# C210_0003_SARA_Module.net
KiCad netlist of a schematic drawn in Altium Designer
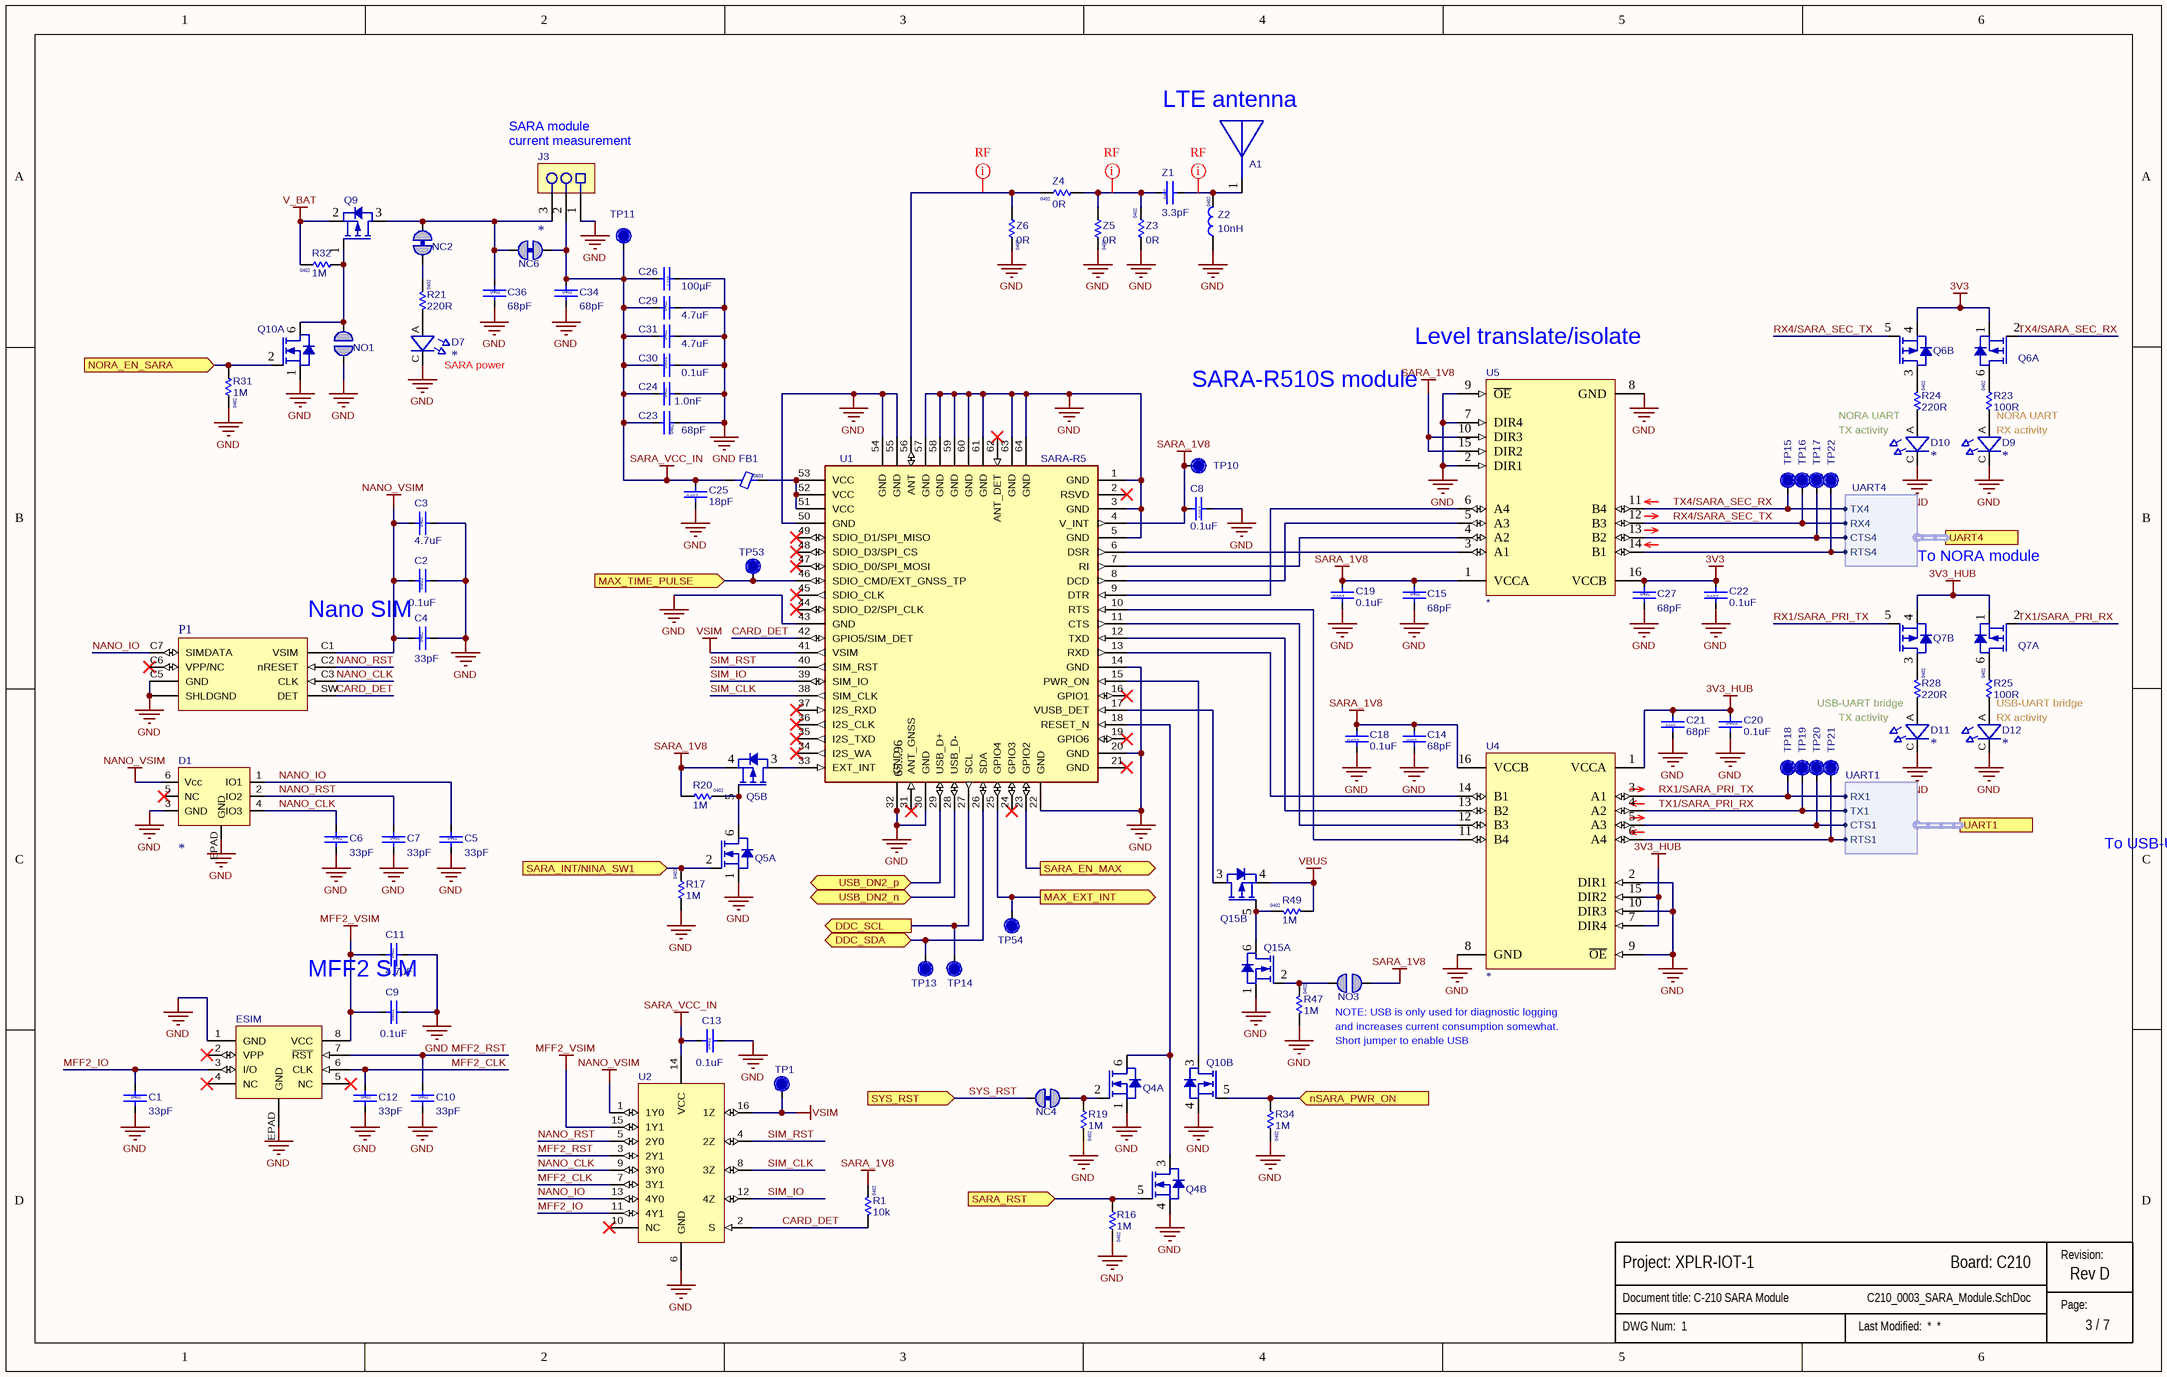
[diagram p0: C210_0003_SARA_Module.SchDoc]

(export (version "E")
  (design (tool "Eeschema 10.0.6"))
  (components
    (comp (ref "A1")
      (value "PCS.66.A")
      (footprint "PCS.66.A")
      (description "RF Passive, Antenna, LTE, 600-6000MHz, Monopole")
      (fields (field (name "VOLTAGE") "None"))
      (libsource (lib "PCS.66.A") (part "PCS.66.A"))
    )
    (comp (ref "C1")
      (value "33pF")
      (footprint "Cap 0402 HD")
      (description "Cap, Ceramic,  33pF, 50V, 5%, NPO, 0402")
      (fields
        (field (name "SIZE") "0402")
        (field (name "PART NUMBER") "120-00045")
        (field (name "TOLERANCE") "+/- 5%")
      )
      (libsource (lib "Arena_Parts_DB_Lib") (part "Cap Chip"))
    )
    (comp (ref "C2")
      (value "0.1uF")
      (footprint "Cap 0402 HD")
      (description "Cap, Ceramic 0.1uF 10V 10% X5R 0402")
      (fields
        (field (name "SIZE") "0402")
        (field (name "PART NUMBER") "120-00016")
        (field (name "MANUFACTURER") "Murata Electronics North America")
      )
      (libsource (lib "Arena_Parts_DB_Lib") (part "Cap Chip"))
    )
    (comp (ref "C3")
      (value "4.7uF")
      (footprint "Cap 0402 HD")
      (description "Cap, Ceramic 4.7uF 10V 20% X5R 0402")
      (fields
        (field (name "SIZE") "0402")
        (field (name "PART NUMBER") "120-00020")
        (field (name "TOLERANCE") "+/- 20%")
      )
      (libsource (lib "Arena_Parts_DB_Lib") (part "Cap Chip"))
    )
    (comp (ref "C4")
      (value "33pF")
      (footprint "Cap 0402 HD")
      (description "Cap, Ceramic,  33pF, 50V, 5%, NPO, 0402")
      (fields
        (field (name "SIZE") "0402")
        (field (name "PART NUMBER") "120-00045")
        (field (name "TOLERANCE") "+/- 5%")
      )
      (libsource (lib "Arena_Parts_DB_Lib") (part "Cap Chip"))
    )
    (comp (ref "C5")
      (value "33pF")
      (footprint "Cap 0402 HD")
      (description "Cap, Ceramic,  33pF, 50V, 5%, NPO, 0402")
      (fields
        (field (name "SIZE") "0402")
        (field (name "PART NUMBER") "120-00045")
        (field (name "TOLERANCE") "+/- 5%")
      )
      (libsource (lib "Arena_Parts_DB_Lib") (part "Cap Chip"))
    )
    (comp (ref "C6")
      (value "33pF")
      (footprint "Cap 0402 HD")
      (description "Cap, Ceramic,  33pF, 50V, 5%, NPO, 0402")
      (fields
        (field (name "SIZE") "0402")
        (field (name "PART NUMBER") "120-00045")
        (field (name "TOLERANCE") "+/- 5%")
      )
      (libsource (lib "Arena_Parts_DB_Lib") (part "Cap Chip"))
    )
    (comp (ref "C7")
      (value "33pF")
      (footprint "Cap 0402 HD")
      (description "Cap, Ceramic,  33pF, 50V, 5%, NPO, 0402")
      (fields
        (field (name "SIZE") "0402")
        (field (name "PART NUMBER") "120-00045")
        (field (name "TOLERANCE") "+/- 5%")
      )
      (libsource (lib "Arena_Parts_DB_Lib") (part "Cap Chip"))
    )
    (comp (ref "C8")
      (value "0.1uF")
      (footprint "Cap 0402 HD")
      (description "Cap, Ceramic 0.1uF 10V 10% X5R 0402")
      (fields
        (field (name "SIZE") "0402")
        (field (name "PART NUMBER") "120-00016")
        (field (name "MANUFACTURER") "Murata Electronics North America")
      )
      (libsource (lib "Arena_Parts_DB_Lib") (part "Cap Chip"))
    )
    (comp (ref "C9")
      (value "0.1uF")
      (footprint "Cap 0402 HD")
      (description "Cap, Ceramic 0.1uF 10V 10% X5R 0402")
      (fields
        (field (name "SIZE") "0402")
        (field (name "PART NUMBER") "120-00016")
        (field (name "MANUFACTURER") "Murata Electronics North America")
      )
      (libsource (lib "Arena_Parts_DB_Lib") (part "Cap Chip"))
    )
    (comp (ref "C10")
      (value "33pF")
      (footprint "Cap 0402 HD")
      (description "Cap, Ceramic,  33pF, 50V, 5%, NPO, 0402")
      (fields
        (field (name "SIZE") "0402")
        (field (name "PART NUMBER") "120-00045")
        (field (name "TOLERANCE") "+/- 5%")
      )
      (libsource (lib "Arena_Parts_DB_Lib") (part "Cap Chip"))
    )
    (comp (ref "C11")
      (value "4.7uF")
      (footprint "Cap 0402 HD")
      (description "Cap, Ceramic 4.7uF 10V 20% X5R 0402")
      (fields
        (field (name "SIZE") "0402")
        (field (name "PART NUMBER") "120-00020")
        (field (name "TOLERANCE") "+/- 20%")
      )
      (libsource (lib "Arena_Parts_DB_Lib") (part "Cap Chip"))
    )
    (comp (ref "C12")
      (value "33pF")
      (footprint "Cap 0402 HD")
      (description "Cap, Ceramic,  33pF, 50V, 5%, NPO, 0402")
      (fields
        (field (name "SIZE") "0402")
        (field (name "PART NUMBER") "120-00045")
        (field (name "TOLERANCE") "+/- 5%")
      )
      (libsource (lib "Arena_Parts_DB_Lib") (part "Cap Chip"))
    )
    (comp (ref "C13")
      (value "0.1uF")
      (footprint "Cap 0402 HD")
      (description "Cap, Ceramic 0.1uF 10V 10% X5R 0402")
      (fields
        (field (name "SIZE") "0402")
        (field (name "PART NUMBER") "120-00016")
        (field (name "MANUFACTURER") "Murata Electronics North America")
      )
      (libsource (lib "Arena_Parts_DB_Lib") (part "Cap Chip"))
    )
    (comp (ref "C14")
      (value "68pF")
      (footprint "Cap 0402 HD")
      (description "Cap, Ceramic, 68pF, 50V, 1%, NP0, 0402")
      (fields
        (field (name "SIZE") "0402")
        (field (name "PART NUMBER") "120-00047")
        (field (name "TOLERANCE") "+/- 1%")
      )
      (libsource (lib "Arena_Parts_DB_Lib") (part "Cap Chip"))
    )
    (comp (ref "C15")
      (value "68pF")
      (footprint "Cap 0402 HD")
      (description "Cap, Ceramic, 68pF, 50V, 1%, NP0, 0402")
      (fields
        (field (name "SIZE") "0402")
        (field (name "PART NUMBER") "120-00047")
        (field (name "TOLERANCE") "+/- 1%")
      )
      (libsource (lib "Arena_Parts_DB_Lib") (part "Cap Chip"))
    )
    (comp (ref "C18")
      (value "0.1uF")
      (footprint "Cap 0402 HD")
      (description "Cap, Ceramic 0.1uF 10V 10% X5R 0402")
      (fields
        (field (name "SIZE") "0402")
        (field (name "PART NUMBER") "120-00016")
        (field (name "MANUFACTURER") "Murata Electronics North America")
      )
      (libsource (lib "Arena_Parts_DB_Lib") (part "Cap Chip"))
    )
    (comp (ref "C19")
      (value "0.1uF")
      (footprint "Cap 0402 HD")
      (description "Cap, Ceramic 0.1uF 10V 10% X5R 0402")
      (fields
        (field (name "SIZE") "0402")
        (field (name "PART NUMBER") "120-00016")
        (field (name "MANUFACTURER") "Murata Electronics North America")
      )
      (libsource (lib "Arena_Parts_DB_Lib") (part "Cap Chip"))
    )
    (comp (ref "C20")
      (value "0.1uF")
      (footprint "Cap 0402 HD")
      (description "Cap, Ceramic 0.1uF 10V 10% X5R 0402")
      (fields
        (field (name "SIZE") "0402")
        (field (name "PART NUMBER") "120-00016")
        (field (name "MANUFACTURER") "Murata Electronics North America")
      )
      (libsource (lib "Arena_Parts_DB_Lib") (part "Cap Chip"))
    )
    (comp (ref "C21")
      (value "68pF")
      (footprint "Cap 0402 HD")
      (description "Cap, Ceramic, 68pF, 50V, 1%, NP0, 0402")
      (fields
        (field (name "SIZE") "0402")
        (field (name "PART NUMBER") "120-00047")
        (field (name "TOLERANCE") "+/- 1%")
      )
      (libsource (lib "Arena_Parts_DB_Lib") (part "Cap Chip"))
    )
    (comp (ref "C22")
      (value "0.1uF")
      (footprint "Cap 0402 HD")
      (description "Cap, Ceramic 0.1uF 10V 10% X5R 0402")
      (fields
        (field (name "SIZE") "0402")
        (field (name "PART NUMBER") "120-00016")
        (field (name "MANUFACTURER") "Murata Electronics North America")
      )
      (libsource (lib "Arena_Parts_DB_Lib") (part "Cap Chip"))
    )
    (comp (ref "C23")
      (value "68pF")
      (footprint "Cap 0402 HD")
      (description "Cap, Ceramic, 68pF, 50V, 1%, NP0, 0402")
      (fields
        (field (name "SIZE") "0402")
        (field (name "PART NUMBER") "120-00047")
        (field (name "TOLERANCE") "+/- 1%")
      )
      (libsource (lib "Arena_Parts_DB_Lib") (part "Cap Chip"))
    )
    (comp (ref "C24")
      (value "1.0nF")
      (footprint "Cap 0402 HD")
      (description "CAP CER 1.0nF 50V 10% X7R 0402")
      (fields
        (field (name "SIZE") "0402")
        (field (name "PART NUMBER") "120-00010")
        (field (name "TOLERANCE") "+/- 10%")
      )
      (libsource (lib "Arena_Parts_DB_Lib") (part "Cap Chip"))
    )
    (comp (ref "C25")
      (value "18pF")
      (footprint "Cap 0402 HD")
      (description "Cap, Ceramic 18pF 50V 5% NP0 0402")
      (fields
        (field (name "SIZE") "0402")
        (field (name "PART NUMBER") "120-00041")
        (field (name "TOLERANCE") "+/- 5%")
      )
      (libsource (lib "Arena_Parts_DB_Lib") (part "Cap Chip"))
    )
    (comp (ref "C26")
      (value "100µF")
      (footprint "Cap 1210")
      (description "100µF ±20% 10V Ceramic Capacitor X5R 1210 (3225 Metric)")
      (fields
        (field (name "SIZE") "1210")
        (field (name "PART NUMBER") "120-00223")
        (field (name "TOLERANCE") "+/- 20%")
      )
      (libsource (lib "Arena_Parts_DB_Lib") (part "Cap Chip"))
    )
    (comp (ref "C27")
      (value "68pF")
      (footprint "Cap 0402 HD")
      (description "Cap, Ceramic, 68pF, 50V, 1%, NP0, 0402")
      (fields
        (field (name "SIZE") "0402")
        (field (name "PART NUMBER") "120-00047")
        (field (name "TOLERANCE") "+/- 1%")
      )
      (libsource (lib "Arena_Parts_DB_Lib") (part "Cap Chip"))
    )
    (comp (ref "C29")
      (value "4.7uF")
      (footprint "Cap 0402 HD")
      (description "Cap, Ceramic 4.7uF 10V 20% X5R 0402")
      (fields
        (field (name "SIZE") "0402")
        (field (name "PART NUMBER") "120-00020")
        (field (name "TOLERANCE") "+/- 20%")
      )
      (libsource (lib "Arena_Parts_DB_Lib") (part "Cap Chip"))
    )
    (comp (ref "C30")
      (value "0.1uF")
      (footprint "Cap 0402 HD")
      (description "Cap, Ceramic 0.1uF 10V 10% X5R 0402")
      (fields
        (field (name "SIZE") "0402")
        (field (name "PART NUMBER") "120-00016")
        (field (name "MANUFACTURER") "Murata Electronics North America")
      )
      (libsource (lib "Arena_Parts_DB_Lib") (part "Cap Chip"))
    )
    (comp (ref "C31")
      (value "4.7uF")
      (footprint "Cap 0402 HD")
      (description "Cap, Ceramic 4.7uF 10V 20% X5R 0402")
      (fields
        (field (name "SIZE") "0402")
        (field (name "PART NUMBER") "120-00020")
        (field (name "TOLERANCE") "+/- 20%")
      )
      (libsource (lib "Arena_Parts_DB_Lib") (part "Cap Chip"))
    )
    (comp (ref "C34")
      (value "68pF")
      (footprint "Cap 0402 HD")
      (description "Cap, Ceramic, 68pF, 50V, 1%, NP0, 0402")
      (fields
        (field (name "SIZE") "0402")
        (field (name "PART NUMBER") "120-00047")
        (field (name "TOLERANCE") "+/- 1%")
      )
      (libsource (lib "Arena_Parts_DB_Lib") (part "Cap Chip"))
    )
    (comp (ref "C36")
      (value "68pF")
      (footprint "Cap 0402 HD")
      (description "Cap, Ceramic, 68pF, 50V, 1%, NP0, 0402")
      (fields
        (field (name "SIZE") "0402")
        (field (name "PART NUMBER") "120-00047")
        (field (name "TOLERANCE") "+/- 1%")
      )
      (libsource (lib "Arena_Parts_DB_Lib") (part "Cap Chip"))
    )
    (comp (ref "D1")
      (value "~")
      (footprint "TPD3E001DRSR")
      (description "TVS Diode, ESD High Speed 3-Channel Array, WSON-6, 3mmX3mm")
      (fields (field (name "VOLTAGE") "5.5V") (field (name "MANUFACTURER P/N") "*"))
      (libsource (lib "TPD3E001DRSR") (part "TPD3E001"))
    )
    (comp (ref "D7")
      (value "LTST-C190EKT")
      (footprint "LTST-C190EKT")
      (description "DIODE, LED, SMT, Red, CLEAR LENS, 2.0V 10mA, 0603")
      (fields (field (name "VOLTAGE") "2.0V") (field (name "COLOR") "*"))
      (libsource (lib "LTST-C190EKT") (part "LTST-C190EKT"))
    )
    (comp (ref "D9")
      (value "LTST-C190YKT")
      (footprint "LTST-C190YKT")
      (description "DIODE, LED, SMT, YELLOW, CLEAR LENS, 2.1V 10mA, 0603")
      (fields (field (name "VOLTAGE") "2.1V") (field (name "COLOR") "*"))
      (libsource (lib "LTST-C190YKT") (part "LTST-C190YKT"))
    )
    (comp (ref "D10")
      (value "115-00019")
      (footprint "LTST-C190KGKT")
      (description "DIODE, LED, SMT, GREEN, CLEAR LENS, 2.0V 20mA, 0603")
      (fields (field (name "VOLTAGE") "2.0V") (field (name "COLOR") "*"))
      (libsource (lib "LTST-C190KGKT") (part "LTST-C190KGKT"))
    )
    (comp (ref "D11")
      (value "115-00019")
      (footprint "LTST-C190KGKT")
      (description "DIODE, LED, SMT, GREEN, CLEAR LENS, 2.0V 20mA, 0603")
      (fields (field (name "VOLTAGE") "2.0V") (field (name "COLOR") "*"))
      (libsource (lib "LTST-C190KGKT") (part "LTST-C190KGKT"))
    )
    (comp (ref "D12")
      (value "LTST-C190YKT")
      (footprint "LTST-C190YKT")
      (description "DIODE, LED, SMT, YELLOW, CLEAR LENS, 2.1V 10mA, 0603")
      (fields (field (name "VOLTAGE") "2.1V") (field (name "COLOR") "*"))
      (libsource (lib "LTST-C190YKT") (part "LTST-C190YKT"))
    )
    (comp (ref "ESIM")
      (value "MFF2 SIM")
      (footprint "MFF2 SIM")
      (description "ESIM, SMT, MFF2, 1.8V, SMT, VFDFPN8, 5mmX6mm")
      (fields (field (name "VOLTAGE") "1.8V"))
      (libsource (lib "MFF2") (part "MFF2 SIM"))
    )
    (comp (ref "FB1")
      (value "BLM18EG221SN1")
      (footprint "BLM18EG221SN1")
      (description "Ferrite Bead, 220ohm @ 100MHz, 2A, 0603")
      (fields (field (name "VOLTAGE") "None") (field (name "SIZE") "0603"))
      (libsource (lib "BLM18EG221SN1") (part "BLM18EG221SN1"))
    )
    (comp (ref "J3")
      (value "130-00105")
      (footprint "HDR-0.1P-3Pin-1Row-SMT")
      (description "Header, 0.100\" Pitch, 3 Pin, Vertical SMT, Black")
      (fields (field (name "MANUFACTURER P/N") "*") (field (name "VOLTAGE") "None"))
      (libsource (lib "Arena_Parts_DB_Lib") (part "CON-3Pin_1Row"))
    )
    (comp (ref "NC2")
      (value "Solderbridge-ShortDNP")
      (footprint "Solderbridge-Short")
      (description "Solderbridge-Short")
      (fields (field (name "ADDED BY") "Paul B"))
      (libsource (lib "PCB_Misc") (part "Solderbridge-Short"))
    )
    (comp (ref "NC4")
      (value "Solderbridge-ShortDNP")
      (footprint "Solderbridge-Short")
      (description "Solderbridge-Short")
      (fields (field (name "ADDED BY") "Paul B"))
      (libsource (lib "") (part "Solderbridge-Short_1"))
    )
    (comp (ref "NC6")
      (value "Solderbridge-ShortDNP")
      (footprint "Solderbridge-Short")
      (description "Solderbridge-Short")
      (fields (field (name "ADDED BY") "Paul B"))
      (libsource (lib "") (part "Solderbridge-Short_1"))
    )
    (comp (ref "NO1")
      (value "Solderbridge-OpenDNP")
      (footprint "Solderbridge-Open")
      (description "Solderbridge-Open")
      (fields (field (name "ADDED BY") "Paul B"))
      (libsource (lib "PCB_Misc") (part "Solderbridge-Open"))
    )
    (comp (ref "NO3")
      (value "Solderbridge-OpenDNP")
      (footprint "Solderbridge-Open")
      (description "Solderbridge-Open")
      (fields (field (name "ADDED BY") "Paul B"))
      (libsource (lib "PCB_Misc") (part "Solderbridge-Open"))
    )
    (comp (ref "P1")
      (value "G85D1160022HHR")
      (footprint "G85D1160022HHR")
      (description "NANO SIM SOCKET, SWITCH, SMT, HINGED, 13mmX14mm")
      (fields (field (name "VOLTAGE") "5V"))
      (libsource (lib "DM3CS-SF") (part "G85D1160022HHR"))
    )
    (comp (ref "Q4")
      (value "140-00016")
      (footprint "SOT-563")
      (description "MOSFET 2N-CH 20V 0.8A, SOT-563")
      (fields (field (name "VOLTAGE") "20V"))
      (libsource (lib "Arena_Parts_DB_Lib") (part "MOSFET-N-Dual"))
    )
    (comp (ref "Q5")
      (value "140-00030")
      (footprint "SOT-563")
      (description "MOSFET N/P-CH 20V SOT-563, 540 mA, −430 mA")
      (fields (field (name "VOLTAGE") "20V"))
      (libsource (lib "Arena_Parts_DB_Lib") (part "MOSFET-N-P_Pair"))
    )
    (comp (ref "Q6")
      (value "FDY2000PZ")
      (footprint "FDY2000PZ")
      (description "MOSFET DUAL P-CH 20V SOT-563, -350mA")
      (fields (field (name "VOLTAGE") "20V"))
      (libsource (lib "FDY2000PZ") (part "MOSFET-Dual-P_Chan"))
    )
    (comp (ref "Q7")
      (value "FDY2000PZ")
      (footprint "FDY2000PZ")
      (description "MOSFET DUAL P-CH 20V SOT-563, -350mA")
      (fields (field (name "VOLTAGE") "20V"))
      (libsource (lib "FDY2000PZ") (part "MOSFET-Dual-P_Chan"))
    )
    (comp (ref "Q9")
      (value "140-00008")
      (footprint "SOT-23")
      (description "P-MOSFET, 20V 3.1A, SOT-23")
      (fields (field (name "VOLTAGE") "20V"))
      (libsource (lib "Arena_Parts_DB_Lib") (part "MOSFET-P"))
    )
    (comp (ref "Q10")
      (value "140-00016")
      (footprint "SOT-563")
      (description "MOSFET 2N-CH 20V 0.8A, SOT-563")
      (fields (field (name "VOLTAGE") "20V"))
      (libsource (lib "Arena_Parts_DB_Lib") (part "MOSFET-N-Dual"))
    )
    (comp (ref "Q15")
      (value "140-00030")
      (footprint "SOT-563")
      (description "MOSFET N/P-CH 20V SOT-563, 540 mA, −430 mA")
      (fields (field (name "VOLTAGE") "20V"))
      (libsource (lib "Arena_Parts_DB_Lib") (part "MOSFET-N-P_Pair"))
    )
    (comp (ref "R1")
      (value "10k")
      (footprint "RES 0402 HD")
      (description "Resistor 10k ohm 1% 1/16W, 0402")
      (fields
        (field (name "SIZE") "0402")
        (field (name "PART NUMBER") "180-00024")
        (field (name "POWER") "1/16W")
      )
      (libsource (lib "Arena_Parts_DB_Lib") (part "Res sm"))
    )
    (comp (ref "R16")
      (value "1M")
      (footprint "RES 0402 HD")
      (description "Resistor 1M ohm 1%, 1/16W, 0402")
      (fields
        (field (name "SIZE") "0402")
        (field (name "PART NUMBER") "180-00054")
        (field (name "POWER") "1/16W")
      )
      (libsource (lib "Arena_Parts_DB_Lib") (part "Res sm"))
    )
    (comp (ref "R17")
      (value "1M")
      (footprint "RES 0402 HD")
      (description "Resistor 1M ohm 1%, 1/16W, 0402")
      (fields
        (field (name "SIZE") "0402")
        (field (name "PART NUMBER") "180-00054")
        (field (name "POWER") "1/16W")
      )
      (libsource (lib "Arena_Parts_DB_Lib") (part "Res sm"))
    )
    (comp (ref "R19")
      (value "1M")
      (footprint "RES 0402 HD")
      (description "Resistor 1M ohm 1%, 1/16W, 0402")
      (fields
        (field (name "SIZE") "0402")
        (field (name "PART NUMBER") "180-00054")
        (field (name "POWER") "1/16W")
      )
      (libsource (lib "Arena_Parts_DB_Lib") (part "Res sm"))
    )
    (comp (ref "R20")
      (value "1M")
      (footprint "RES 0402 HD")
      (description "Resistor 1M ohm 1%, 1/16W, 0402")
      (fields
        (field (name "SIZE") "0402")
        (field (name "PART NUMBER") "180-00054")
        (field (name "POWER") "1/16W")
      )
      (libsource (lib "Arena_Parts_DB_Lib") (part "Res sm"))
    )
    (comp (ref "R21")
      (value "220R")
      (footprint "RES 0402 HD")
      (description "Resistor, 220ohm, 5%, 1/16W, 0402.")
      (fields
        (field (name "SIZE") "0402")
        (field (name "PART NUMBER") "180-00098")
        (field (name "MANUFACTURER") "Panasonic Electronic Components")
      )
      (libsource (lib "Arena_Parts_DB_Lib") (part "Res sm"))
    )
    (comp (ref "R23")
      (value "100R")
      (footprint "RES 0402 HD")
      (description "Resistor, 100ohm, 1%, 1/16W, 0402.")
      (fields
        (field (name "SIZE") "0402")
        (field (name "PART NUMBER") "180-00051")
        (field (name "POWER") "1/16W")
      )
      (libsource (lib "Arena_Parts_DB_Lib") (part "Res sm"))
    )
    (comp (ref "R24")
      (value "220R")
      (footprint "RES 0402 HD")
      (description "Resistor, 220ohm, 5%, 1/16W, 0402.")
      (fields
        (field (name "SIZE") "0402")
        (field (name "PART NUMBER") "180-00098")
        (field (name "MANUFACTURER") "Panasonic Electronic Components")
      )
      (libsource (lib "Arena_Parts_DB_Lib") (part "Res sm"))
    )
    (comp (ref "R25")
      (value "100R")
      (footprint "RES 0402 HD")
      (description "Resistor, 100ohm, 1%, 1/16W, 0402.")
      (fields
        (field (name "SIZE") "0402")
        (field (name "PART NUMBER") "180-00051")
        (field (name "POWER") "1/16W")
      )
      (libsource (lib "Arena_Parts_DB_Lib") (part "Res sm"))
    )
    (comp (ref "R28")
      (value "220R")
      (footprint "RES 0402 HD")
      (description "Resistor, 220ohm, 5%, 1/16W, 0402.")
      (fields
        (field (name "SIZE") "0402")
        (field (name "PART NUMBER") "180-00098")
        (field (name "MANUFACTURER") "Panasonic Electronic Components")
      )
      (libsource (lib "Arena_Parts_DB_Lib") (part "Res sm"))
    )
    (comp (ref "R31")
      (value "1M")
      (footprint "RES 0402 HD")
      (description "Resistor 1M ohm 1%, 1/16W, 0402")
      (fields
        (field (name "SIZE") "0402")
        (field (name "PART NUMBER") "180-00054")
        (field (name "POWER") "1/16W")
      )
      (libsource (lib "Arena_Parts_DB_Lib") (part "Res sm"))
    )
    (comp (ref "R32")
      (value "1M")
      (footprint "RES 0402 HD")
      (description "Resistor 1M ohm 1%, 1/16W, 0402")
      (fields
        (field (name "SIZE") "0402")
        (field (name "PART NUMBER") "180-00054")
        (field (name "POWER") "1/16W")
      )
      (libsource (lib "Arena_Parts_DB_Lib") (part "Res sm"))
    )
    (comp (ref "R34")
      (value "1M")
      (footprint "RES 0402 HD")
      (description "Resistor 1M ohm 1%, 1/16W, 0402")
      (fields
        (field (name "SIZE") "0402")
        (field (name "PART NUMBER") "180-00054")
        (field (name "POWER") "1/16W")
      )
      (libsource (lib "Arena_Parts_DB_Lib") (part "Res sm"))
    )
    (comp (ref "R47")
      (value "1M")
      (footprint "RES 0402 HD")
      (description "Resistor 1M ohm 1%, 1/16W, 0402")
      (fields
        (field (name "SIZE") "0402")
        (field (name "PART NUMBER") "180-00054")
        (field (name "POWER") "1/16W")
      )
      (libsource (lib "Arena_Parts_DB_Lib") (part "Res sm"))
    )
    (comp (ref "R49")
      (value "1M")
      (footprint "RES 0402 HD")
      (description "Resistor 1M ohm 1%, 1/16W, 0402")
      (fields
        (field (name "SIZE") "0402")
        (field (name "PART NUMBER") "180-00054")
        (field (name "POWER") "1/16W")
      )
      (libsource (lib "Arena_Parts_DB_Lib") (part "Res sm"))
    )
    (comp (ref "TP1")
      (value "TP")
      (footprint "TP12R")
      (description "Testpoint, Round 1.0mm Dia")
      (fields
        (field (name "PART NUMBER") "TP10R")
        (field (name "ADDED BY") "Jeremy D")
        (field (name "CHECKED BY") "Paul B")
      )
      (libsource (lib "PCB_Misc") (part "TP_R"))
    )
    (comp (ref "TP10")
      (value "TP")
      (footprint "TP12R")
      (description "Testpoint, Round 1.0mm Dia")
      (fields
        (field (name "PART NUMBER") "TP10R")
        (field (name "ADDED BY") "Jeremy D")
        (field (name "CHECKED BY") "Paul B")
      )
      (libsource (lib "PCB_Misc") (part "TP_R"))
    )
    (comp (ref "TP11")
      (value "TP")
      (footprint "TP12R")
      (description "Testpoint, Round 1.0mm Dia")
      (fields
        (field (name "PART NUMBER") "TP10R")
        (field (name "ADDED BY") "Jeremy D")
        (field (name "CHECKED BY") "Paul B")
      )
      (libsource (lib "PCB_Misc") (part "TP_R"))
    )
    (comp (ref "TP13")
      (value "TP")
      (footprint "TP12R")
      (description "Testpoint, Round 1.0mm Dia")
      (fields
        (field (name "PART NUMBER") "TP10R")
        (field (name "ADDED BY") "Jeremy D")
        (field (name "CHECKED BY") "Paul B")
      )
      (libsource (lib "PCB_Misc") (part "TP_R"))
    )
    (comp (ref "TP14")
      (value "TP")
      (footprint "TP12R")
      (description "Testpoint, Round 1.0mm Dia")
      (fields
        (field (name "PART NUMBER") "TP10R")
        (field (name "ADDED BY") "Jeremy D")
        (field (name "CHECKED BY") "Paul B")
      )
      (libsource (lib "PCB_Misc") (part "TP_R"))
    )
    (comp (ref "TP15")
      (value "TP")
      (footprint "TP12R")
      (description "Testpoint, Round 1.0mm Dia")
      (fields
        (field (name "PART NUMBER") "TP10R")
        (field (name "ADDED BY") "Jeremy D")
        (field (name "CHECKED BY") "Paul B")
      )
      (libsource (lib "PCB_Misc") (part "TP_R"))
    )
    (comp (ref "TP16")
      (value "TP")
      (footprint "TP12R")
      (description "Testpoint, Round 1.0mm Dia")
      (fields
        (field (name "PART NUMBER") "TP10R")
        (field (name "ADDED BY") "Jeremy D")
        (field (name "CHECKED BY") "Paul B")
      )
      (libsource (lib "PCB_Misc") (part "TP_R"))
    )
    (comp (ref "TP17")
      (value "TP")
      (footprint "TP12R")
      (description "Testpoint, Round 1.0mm Dia")
      (fields
        (field (name "PART NUMBER") "TP10R")
        (field (name "ADDED BY") "Jeremy D")
        (field (name "CHECKED BY") "Paul B")
      )
      (libsource (lib "PCB_Misc") (part "TP_R"))
    )
    (comp (ref "TP18")
      (value "TP")
      (footprint "TP12R")
      (description "Testpoint, Round 1.0mm Dia")
      (fields
        (field (name "PART NUMBER") "TP10R")
        (field (name "ADDED BY") "Jeremy D")
        (field (name "CHECKED BY") "Paul B")
      )
      (libsource (lib "PCB_Misc") (part "TP_R"))
    )
    (comp (ref "TP19")
      (value "TP")
      (footprint "TP12R")
      (description "Testpoint, Round 1.0mm Dia")
      (fields
        (field (name "PART NUMBER") "TP10R")
        (field (name "ADDED BY") "Jeremy D")
        (field (name "CHECKED BY") "Paul B")
      )
      (libsource (lib "PCB_Misc") (part "TP_R"))
    )
    (comp (ref "TP20")
      (value "TP")
      (footprint "TP12R")
      (description "Testpoint, Round 1.0mm Dia")
      (fields
        (field (name "PART NUMBER") "TP10R")
        (field (name "ADDED BY") "Jeremy D")
        (field (name "CHECKED BY") "Paul B")
      )
      (libsource (lib "PCB_Misc") (part "TP_R"))
    )
    (comp (ref "TP21")
      (value "TP")
      (footprint "TP12R")
      (description "Testpoint, Round 1.0mm Dia")
      (fields
        (field (name "PART NUMBER") "TP10R")
        (field (name "ADDED BY") "Jeremy D")
        (field (name "CHECKED BY") "Paul B")
      )
      (libsource (lib "PCB_Misc") (part "TP_R"))
    )
    (comp (ref "TP22")
      (value "TP")
      (footprint "TP12R")
      (description "Testpoint, Round 1.0mm Dia")
      (fields
        (field (name "PART NUMBER") "TP10R")
        (field (name "ADDED BY") "Jeremy D")
        (field (name "CHECKED BY") "Paul B")
      )
      (libsource (lib "PCB_Misc") (part "TP_R"))
    )
    (comp (ref "TP53")
      (value "TP")
      (footprint "TP12R")
      (description "Testpoint, Round 1.0mm Dia")
      (fields
        (field (name "PART NUMBER") "TP10R")
        (field (name "ADDED BY") "Jeremy D")
        (field (name "CHECKED BY") "Paul B")
      )
      (libsource (lib "PCB_Misc") (part "TP_R"))
    )
    (comp (ref "TP54")
      (value "TP")
      (footprint "TP12R")
      (description "Testpoint, Round 1.0mm Dia")
      (fields
        (field (name "PART NUMBER") "TP10R")
        (field (name "ADDED BY") "Jeremy D")
        (field (name "CHECKED BY") "Paul B")
      )
      (libsource (lib "PCB_Misc") (part "TP_R"))
    )
    (comp (ref "U1")
      (value "SARA-R5")
      (footprint "SARA-XX")
      (description "GSM/GPRS and GSM/EGPRS/HSPA Cellular Module")
      (fields (field (name "MANUFACTURER") "u-blox"))
      (libsource (lib "ubloxLib") (part "SARA-R5"))
    )
    (comp (ref "U2")
      (value "NX3DV2567")
      (footprint "XQFN-16")
      (description "IC, ANLG SWITCH, 4PDT, SIM OPTIMIZED, 1.4V-4.3V, SMT, XQFN-16, 2.6mmX1.8mm")
      (fields (field (name "VOLTAGE") "1.4V-4.3V"))
      (libsource (lib "NX3DV2567") (part "NX3DV2567"))
    )
    (comp (ref "U4")
      (value "225-00011")
      (footprint "QFN0.5P2x6-16Pin_W-Pad")
      (description "Voltage Level Translator Bidirectional 1 Circuit 4 Channel 380Mbps 16-DHVQFN (2.5x3.5)")
      (fields (field (name "MANUFACTURER P/N") "*") (field (name "VOLTAGE") "3.6V"))
      (libsource (lib "") (part "74AVC4TD245_1"))
    )
    (comp (ref "U5")
      (value "225-00011")
      (footprint "QFN0.5P2x6-16Pin_W-Pad")
      (description "Voltage Level Translator Bidirectional 1 Circuit 4 Channel 380Mbps 16-DHVQFN (2.5x3.5)")
      (fields (field (name "MANUFACTURER P/N") "*") (field (name "VOLTAGE") "3.6V"))
      (libsource (lib "Arena_Parts_DB_Lib") (part "74AVC4TD245"))
    )
    (comp (ref "Z1")
      (value "3.3pF")
      (footprint "Cap 0402 HD")
      (description "CAP CER 3.3PF 50V +/-0.25pF NP0 0402")
      (fields
        (field (name "SIZE") "0402")
        (field (name "PART NUMBER") "120-00079")
        (field (name "TOLERANCE") "Other")
      )
      (libsource (lib "Arena_Parts_DB_Lib") (part "Cap Chip"))
    )
    (comp (ref "Z2")
      (value "10nH")
      (footprint "IND 0402")
      (description "INDUCTOR 10NH 300MA 0402")
      (fields
        (field (name "SIZE") "0402")
        (field (name "PART NUMBER") "150-00010")
        (field (name "TOLERANCE") "+/- 5%")
      )
      (libsource (lib "Arena_Parts_DB_Lib") (part "Ind sm"))
    )
    (comp (ref "Z3")
      (value "0R")
      (footprint "RES 0402 HD")
      (description "Resistor 0 ohm 1/16W 0402")
      (fields
        (field (name "SIZE") "0402")
        (field (name "PART NUMBER") "180-00020")
        (field (name "POWER") "1/16W")
      )
      (libsource (lib "Arena_Parts_DB_Lib") (part "Res sm"))
    )
    (comp (ref "Z4")
      (value "0R")
      (footprint "RES 0402 HD")
      (description "Resistor 0 ohm 1/16W 0402")
      (fields
        (field (name "SIZE") "0402")
        (field (name "PART NUMBER") "180-00020")
        (field (name "POWER") "1/16W")
      )
      (libsource (lib "Arena_Parts_DB_Lib") (part "Res sm"))
    )
    (comp (ref "Z5")
      (value "0R")
      (footprint "RES 0402 HD")
      (description "Resistor 0 ohm 1/16W 0402")
      (fields
        (field (name "SIZE") "0402")
        (field (name "PART NUMBER") "180-00020")
        (field (name "POWER") "1/16W")
      )
      (libsource (lib "Arena_Parts_DB_Lib") (part "Res sm"))
    )
    (comp (ref "Z6")
      (value "0R")
      (footprint "RES 0402 HD")
      (description "Resistor 0 ohm 1/16W 0402")
      (fields
        (field (name "SIZE") "0402")
        (field (name "PART NUMBER") "180-00020")
        (field (name "POWER") "1/16W")
      )
      (libsource (lib "Arena_Parts_DB_Lib") (part "Res sm"))
    )
  )
  (nets
    (net (code "3") (name "/CARD_DET") (class "Default")
      (node (ref "P1") (pin "SW") (pinfunction "DET_SW") (pintype "passive"))
      (node (ref "R1") (pin "1") (pinfunction "1_1") (pintype "passive"))
      (node (ref "U1") (pin "42") (pinfunction "GPIO5/SIM_DET_42") (pintype "bidirectional"))
      (node (ref "U2") (pin "2") (pinfunction "S_2") (pintype "input"))
    )
    (net (code "4") (name "/DDC_SCL") (class "Default")
      (node (ref "TP14") (pin "1") (pintype "passive"))
      (node (ref "U1") (pin "27") (pinfunction "SCL_27") (pintype "output"))
    )
    (net (code "5") (name "/DDC_SDA") (class "Default")
      (node (ref "TP13") (pin "1") (pintype "passive"))
      (node (ref "U1") (pin "26") (pinfunction "SDA_26") (pintype "bidirectional"))
    )
    (net (code "6") (name "/MAX_EXT_INT") (class "Default")
      (node (ref "TP54") (pin "1") (pintype "passive"))
      (node (ref "U1") (pin "25") (pinfunction "GPIO4_25") (pintype "bidirectional"))
    )
    (net (code "7") (name "/MAX_TIME_PULSE") (class "Default")
      (node (ref "TP53") (pin "1") (pintype "passive"))
      (node (ref "U1") (pin "46") (pinfunction "SDIO_CMD/EXT_GNSS_TP_46") (pintype "bidirectional"))
    )
    (net (code "8") (name "/MFF2_CLK") (class "Default")
      (node (ref "C12") (pin "1") (pinfunction "1_1") (pintype "passive"))
      (node (ref "ESIM") (pin "6") (pinfunction "CLK_6") (pintype "input"))
      (node (ref "U2") (pin "7") (pinfunction "3Y1_7") (pintype "bidirectional"))
    )
    (net (code "9") (name "/MFF2_IO") (class "Default")
      (node (ref "C1") (pin "1") (pinfunction "1_1") (pintype "passive"))
      (node (ref "ESIM") (pin "3") (pinfunction "I/O_3") (pintype "bidirectional"))
      (node (ref "U2") (pin "11") (pinfunction "4Y1_11") (pintype "bidirectional"))
    )
    (net (code "10") (name "/MFF2_RST") (class "Default")
      (node (ref "C10") (pin "1") (pinfunction "1_1") (pintype "passive"))
      (node (ref "ESIM") (pin "7") (pinfunction "~{RST}_7") (pintype "input"))
      (node (ref "U2") (pin "3") (pinfunction "2Y1_3") (pintype "bidirectional"))
    )
    (net (code "11") (name "/NANO_CLK") (class "Default")
      (node (ref "C6") (pin "1") (pinfunction "1_1") (pintype "passive"))
      (node (ref "D1") (pin "4") (pinfunction "IO3_4") (pintype "passive"))
      (node (ref "P1") (pin "C3") (pinfunction "CLK_C3") (pintype "input"))
      (node (ref "U2") (pin "9") (pinfunction "3Y0_9") (pintype "bidirectional"))
    )
    (net (code "12") (name "/NANO_IO") (class "Default")
      (node (ref "C5") (pin "1") (pinfunction "1_1") (pintype "passive"))
      (node (ref "D1") (pin "1") (pinfunction "IO1_1") (pintype "passive"))
      (node (ref "P1") (pin "C7") (pinfunction "SIMDATA_C7") (pintype "bidirectional"))
      (node (ref "U2") (pin "13") (pinfunction "4Y0_13") (pintype "bidirectional"))
    )
    (net (code "13") (name "/NANO_RST") (class "Default")
      (node (ref "C7") (pin "1") (pinfunction "1_1") (pintype "passive"))
      (node (ref "D1") (pin "2") (pinfunction "IO2_2") (pintype "passive"))
      (node (ref "P1") (pin "C2") (pinfunction "nRESET_C2") (pintype "input"))
      (node (ref "U2") (pin "5") (pinfunction "2Y0_5") (pintype "bidirectional"))
    )
    (net (code "14") (name "/NORA_EN_SARA") (class "Default")
      (node (ref "Q10") (pin "2") (pinfunction "G1_2") (pintype "passive"))
      (node (ref "R31") (pin "1") (pinfunction "1_1") (pintype "passive"))
    )
    (net (code "15") (name "/RX1{slash}SARA_PRI_TX") (class "Default")
      (node (ref "Q7") (pin "5") (pinfunction "G2_5") (pintype "passive"))
      (node (ref "TP18") (pin "1") (pintype "passive"))
      (node (ref "U4") (pin "3") (pinfunction "A1_3") (pintype "bidirectional"))
    )
    (net (code "16") (name "/RX4{slash}SARA_SEC_TX") (class "Default")
      (node (ref "Q6") (pin "5") (pinfunction "G2_5") (pintype "passive"))
      (node (ref "TP16") (pin "1") (pintype "passive"))
      (node (ref "U5") (pin "12") (pinfunction "B3_12") (pintype "bidirectional"))
    )
    (net (code "17") (name "/SARA_EN_MAX") (class "Default")
      (node (ref "U1") (pin "23") (pinfunction "GPIO2_23") (pintype "bidirectional"))
    )
    (net (code "18") (name "/SARA_INT{slash}NINA_SW1") (class "Default")
      (node (ref "Q5") (pin "2") (pinfunction "G1_2") (pintype "passive"))
      (node (ref "R17") (pin "2") (pinfunction "2_2") (pintype "passive"))
    )
    (net (code "19") (name "/SARA_RST") (class "Default")
      (node (ref "Q4") (pin "5") (pinfunction "G2_5") (pintype "passive"))
      (node (ref "R16") (pin "1") (pinfunction "1_1") (pintype "passive"))
    )
    (net (code "20") (name "/SIM_CLK") (class "Default")
      (node (ref "U1") (pin "38") (pinfunction "SIM_CLK_38") (pintype "output"))
      (node (ref "U2") (pin "8") (pinfunction "3Z_8") (pintype "bidirectional"))
    )
    (net (code "21") (name "/SIM_IO") (class "Default")
      (node (ref "U1") (pin "39") (pinfunction "SIM_IO_39") (pintype "bidirectional"))
      (node (ref "U2") (pin "12") (pinfunction "4Z_12") (pintype "bidirectional"))
    )
    (net (code "22") (name "/SIM_RST") (class "Default")
      (node (ref "U1") (pin "40") (pinfunction "SIM_RST_40") (pintype "output"))
      (node (ref "U2") (pin "4") (pinfunction "2Z_4") (pintype "bidirectional"))
    )
    (net (code "23") (name "/SYS_RST") (class "Default")
      (node (ref "NC4") (pin "2") (pinfunction "2_2") (pintype "passive"))
    )
    (net (code "24") (name "/TX1{slash}SARA_PRI_RX") (class "Default")
      (node (ref "Q7") (pin "2") (pinfunction "G1_2") (pintype "passive"))
      (node (ref "TP19") (pin "1") (pintype "passive"))
      (node (ref "U4") (pin "4") (pinfunction "A2_4") (pintype "bidirectional"))
    )
    (net (code "25") (name "/TX4{slash}SARA_SEC_RX") (class "Default")
      (node (ref "Q6") (pin "2") (pinfunction "G1_2") (pintype "passive"))
      (node (ref "TP15") (pin "1") (pintype "passive"))
      (node (ref "U5") (pin "11") (pinfunction "B4_11") (pintype "bidirectional"))
    )
    (net (code "26") (name "/USB_DN2_n") (class "Default")
      (node (ref "U1") (pin "28") (pinfunction "USB_D-_28") (pintype "bidirectional"))
    )
    (net (code "27") (name "/USB_DN2_p") (class "Default")
      (node (ref "U1") (pin "29") (pinfunction "USB_D+_29") (pintype "bidirectional"))
    )
    (net (code "28") (name "/nSARA_PWR_ON") (class "Default")
      (node (ref "Q10") (pin "5") (pinfunction "G2_5") (pintype "passive"))
      (node (ref "R34") (pin "1") (pinfunction "1_1") (pintype "passive"))
    )
    (net (code "31") (name "3V3") (class "Default")
      (node (ref "C22") (pin "2") (pinfunction "2_2") (pintype "passive"))
      (node (ref "C27") (pin "1") (pinfunction "1_1") (pintype "passive"))
      (node (ref "Q6") (pin "1") (pinfunction "S1_1") (pintype "passive"))
      (node (ref "Q6") (pin "4") (pinfunction "S2_4") (pintype "passive"))
      (node (ref "U5") (pin "16") (pinfunction "VCCB_16") (pintype "power_in"))
    )
    (net (code "32") (name "3V3_HUB") (class "Default")
      (node (ref "C20") (pin "1") (pinfunction "1_1") (pintype "passive"))
      (node (ref "C21") (pin "2") (pinfunction "2_2") (pintype "passive"))
      (node (ref "Q7") (pin "1") (pinfunction "S1_1") (pintype "passive"))
      (node (ref "Q7") (pin "4") (pinfunction "S2_4") (pintype "passive"))
      (node (ref "U4") (pin "1") (pinfunction "VCCA_1") (pintype "power_in"))
      (node (ref "U4") (pin "15") (pinfunction "DIR2_15") (pintype "input"))
      (node (ref "U4") (pin "7") (pinfunction "DIR4_7") (pintype "input"))
    )
    (net (code "33") (name "GND") (class "Default")
      (node (ref "C1") (pin "2") (pinfunction "2_2") (pintype "passive"))
      (node (ref "C10") (pin "2") (pinfunction "2_2") (pintype "passive"))
      (node (ref "C11") (pin "2") (pinfunction "2_2") (pintype "passive"))
      (node (ref "C12") (pin "2") (pinfunction "2_2") (pintype "passive"))
      (node (ref "C13") (pin "2") (pinfunction "2_2") (pintype "passive"))
      (node (ref "C14") (pin "1") (pinfunction "1_1") (pintype "passive"))
      (node (ref "C15") (pin "2") (pinfunction "2_2") (pintype "passive"))
      (node (ref "C18") (pin "1") (pinfunction "1_1") (pintype "passive"))
      (node (ref "C19") (pin "1") (pinfunction "1_1") (pintype "passive"))
      (node (ref "C2") (pin "2") (pinfunction "2_2") (pintype "passive"))
      (node (ref "C20") (pin "2") (pinfunction "2_2") (pintype "passive"))
      (node (ref "C21") (pin "1") (pinfunction "1_1") (pintype "passive"))
      (node (ref "C22") (pin "1") (pinfunction "1_1") (pintype "passive"))
      (node (ref "C23") (pin "1") (pinfunction "1_1") (pintype "passive"))
      (node (ref "C24") (pin "2") (pinfunction "2_2") (pintype "passive"))
      (node (ref "C25") (pin "1") (pinfunction "1_1") (pintype "passive"))
      (node (ref "C26") (pin "1") (pinfunction "1_1") (pintype "passive"))
      (node (ref "C27") (pin "2") (pinfunction "2_2") (pintype "passive"))
      (node (ref "C29") (pin "2") (pinfunction "2_2") (pintype "passive"))
      (node (ref "C3") (pin "2") (pinfunction "2_2") (pintype "passive"))
      (node (ref "C30") (pin "2") (pinfunction "2_2") (pintype "passive"))
      (node (ref "C31") (pin "2") (pinfunction "2_2") (pintype "passive"))
      (node (ref "C34") (pin "2") (pinfunction "2_2") (pintype "passive"))
      (node (ref "C36") (pin "2") (pinfunction "2_2") (pintype "passive"))
      (node (ref "C4") (pin "2") (pinfunction "2_2") (pintype "passive"))
      (node (ref "C5") (pin "2") (pinfunction "2_2") (pintype "passive"))
      (node (ref "C6") (pin "2") (pinfunction "2_2") (pintype "passive"))
      (node (ref "C7") (pin "2") (pinfunction "2_2") (pintype "passive"))
      (node (ref "C8") (pin "1") (pinfunction "1_1") (pintype "passive"))
      (node (ref "C9") (pin "2") (pinfunction "2_2") (pintype "passive"))
      (node (ref "D1") (pin "3") (pinfunction "GND_3") (pintype "power_in"))
      (node (ref "D1") (pin "EPAD") (pinfunction "GND_EPAD") (pintype "power_in"))
      (node (ref "D10") (pin "C") (pinfunction "Cathode_C") (pintype "passive"))
      (node (ref "D11") (pin "C") (pinfunction "Cathode_C") (pintype "passive"))
      (node (ref "D12") (pin "C") (pinfunction "Cathode_C") (pintype "passive"))
      (node (ref "D7") (pin "C") (pinfunction "Cathode_C") (pintype "passive"))
      (node (ref "D9") (pin "C") (pinfunction "Cathode_C") (pintype "passive"))
      (node (ref "ESIM") (pin "1") (pinfunction "GND_1") (pintype "power_in"))
      (node (ref "ESIM") (pin "EPAD") (pinfunction "GND_EPAD") (pintype "passive"))
      (node (ref "J3") (pin "1") (pinfunction "1_1") (pintype "passive"))
      (node (ref "NO1") (pin "2") (pinfunction "2_2") (pintype "passive"))
      (node (ref "P1") (pin "C5") (pinfunction "GND_C5") (pintype "power_in"))
      (node (ref "P1") (pin "MP") (pinfunction "SHLDGND_MP") (pintype "power_in"))
      (node (ref "Q10") (pin "1") (pinfunction "S1_1") (pintype "passive"))
      (node (ref "Q10") (pin "4") (pinfunction "S2_4") (pintype "passive"))
      (node (ref "Q15") (pin "1") (pinfunction "S1_1") (pintype "passive"))
      (node (ref "Q4") (pin "1") (pinfunction "S1_1") (pintype "passive"))
      (node (ref "Q4") (pin "4") (pinfunction "S2_4") (pintype "passive"))
      (node (ref "Q5") (pin "1") (pinfunction "S1_1") (pintype "passive"))
      (node (ref "R16") (pin "2") (pinfunction "2_2") (pintype "passive"))
      (node (ref "R17") (pin "1") (pinfunction "1_1") (pintype "passive"))
      (node (ref "R19") (pin "2") (pinfunction "2_2") (pintype "passive"))
      (node (ref "R31") (pin "2") (pinfunction "2_2") (pintype "passive"))
      (node (ref "R34") (pin "2") (pinfunction "2_2") (pintype "passive"))
      (node (ref "R47") (pin "1") (pinfunction "1_1") (pintype "passive"))
      (node (ref "U1") (pin "1") (pinfunction "GND_1") (pintype "power_in"))
      (node (ref "U1") (pin "14") (pinfunction "GND_14") (pintype "power_in"))
      (node (ref "U1") (pin "20") (pinfunction "GND_20") (pintype "power_in"))
      (node (ref "U1") (pin "22") (pinfunction "GND_22") (pintype "power_in"))
      (node (ref "U1") (pin "3") (pinfunction "GND_3") (pintype "power_in"))
      (node (ref "U1") (pin "30") (pinfunction "GND_30") (pintype "power_in"))
      (node (ref "U1") (pin "32") (pinfunction "GND_32") (pintype "power_in"))
      (node (ref "U1") (pin "43") (pinfunction "GND_43") (pintype "power_in"))
      (node (ref "U1") (pin "5") (pinfunction "GND_5") (pintype "power_in"))
      (node (ref "U1") (pin "50") (pinfunction "GND_50") (pintype "power_in"))
      (node (ref "U1") (pin "54") (pinfunction "GND_54") (pintype "power_in"))
      (node (ref "U1") (pin "55") (pinfunction "GND_55") (pintype "power_in"))
      (node (ref "U1") (pin "57") (pinfunction "GND_57") (pintype "power_in"))
      (node (ref "U1") (pin "58") (pinfunction "GND_58") (pintype "power_in"))
      (node (ref "U1") (pin "59") (pinfunction "GND_59") (pintype "power_in"))
      (node (ref "U1") (pin "60") (pinfunction "GND_60") (pintype "power_in"))
      (node (ref "U1") (pin "61") (pinfunction "GND_61") (pintype "power_in"))
      (node (ref "U1") (pin "63") (pinfunction "GND_63") (pintype "power_in"))
      (node (ref "U1") (pin "64") (pinfunction "GND_64") (pintype "power_in"))
      (node (ref "U1") (pin "65") (pinfunction "GND_65") (pintype "passive"))
      (node (ref "U1") (pin "66") (pinfunction "GND_66") (pintype "passive"))
      (node (ref "U1") (pin "67") (pinfunction "GND_67") (pintype "passive"))
      (node (ref "U1") (pin "68") (pinfunction "GND_68") (pintype "passive"))
      (node (ref "U1") (pin "69") (pinfunction "GND_69") (pintype "passive"))
      (node (ref "U1") (pin "70") (pinfunction "GND_70") (pintype "passive"))
      (node (ref "U1") (pin "71") (pinfunction "GND_71") (pintype "passive"))
      (node (ref "U1") (pin "72") (pinfunction "GND_72") (pintype "passive"))
      (node (ref "U1") (pin "73") (pinfunction "GND_73") (pintype "passive"))
      (node (ref "U1") (pin "74") (pinfunction "GND_74") (pintype "passive"))
      (node (ref "U1") (pin "75") (pinfunction "GND_75") (pintype "passive"))
      (node (ref "U1") (pin "76") (pinfunction "GND_76") (pintype "passive"))
      (node (ref "U1") (pin "77") (pinfunction "GND_77") (pintype "passive"))
      (node (ref "U1") (pin "78") (pinfunction "GND_78") (pintype "passive"))
      (node (ref "U1") (pin "79") (pinfunction "GND_79") (pintype "passive"))
      (node (ref "U1") (pin "80") (pinfunction "GND_80") (pintype "passive"))
      (node (ref "U1") (pin "81") (pinfunction "GND_81") (pintype "passive"))
      (node (ref "U1") (pin "82") (pinfunction "GND_82") (pintype "passive"))
      (node (ref "U1") (pin "83") (pinfunction "GND_83") (pintype "passive"))
      (node (ref "U1") (pin "84") (pinfunction "GND_84") (pintype "passive"))
      (node (ref "U1") (pin "85") (pinfunction "GND_85") (pintype "passive"))
      (node (ref "U1") (pin "86") (pinfunction "GND_86") (pintype "passive"))
      (node (ref "U1") (pin "87") (pinfunction "GND_87") (pintype "passive"))
      (node (ref "U1") (pin "88") (pinfunction "GND_88") (pintype "passive"))
      (node (ref "U1") (pin "89") (pinfunction "GND_89") (pintype "passive"))
      (node (ref "U1") (pin "90") (pinfunction "GND_90") (pintype "passive"))
      (node (ref "U1") (pin "91") (pinfunction "GND_91") (pintype "passive"))
      (node (ref "U1") (pin "92") (pinfunction "GND_92") (pintype "passive"))
      (node (ref "U1") (pin "93") (pinfunction "GND_93") (pintype "passive"))
      (node (ref "U1") (pin "94") (pinfunction "GND_94") (pintype "passive"))
      (node (ref "U1") (pin "95") (pinfunction "GND_95") (pintype "passive"))
      (node (ref "U1") (pin "96") (pinfunction "GND_96") (pintype "passive"))
      (node (ref "U2") (pin "6") (pinfunction "GND_6") (pintype "power_in"))
      (node (ref "U4") (pin "10") (pinfunction "DIR3_10") (pintype "input"))
      (node (ref "U4") (pin "2") (pinfunction "DIR1_2") (pintype "input"))
      (node (ref "U4") (pin "8") (pinfunction "GND_8") (pintype "power_in"))
      (node (ref "U4") (pin "9") (pinfunction "~{OE}_9") (pintype "input"))
      (node (ref "U5") (pin "2") (pinfunction "DIR1_2") (pintype "input"))
      (node (ref "U5") (pin "7") (pinfunction "DIR4_7") (pintype "input"))
      (node (ref "U5") (pin "8") (pinfunction "GND_8") (pintype "power_in"))
      (node (ref "U5") (pin "9") (pinfunction "~{OE}_9") (pintype "input"))
      (node (ref "Z2") (pin "1") (pinfunction "1_1") (pintype "passive"))
      (node (ref "Z3") (pin "1") (pinfunction "1_1") (pintype "passive"))
      (node (ref "Z5") (pin "2") (pinfunction "2_2") (pintype "passive"))
      (node (ref "Z6") (pin "2") (pinfunction "2_2") (pintype "passive"))
    )
    (net (code "34") (name "MFF2_VSIM") (class "Default")
      (node (ref "C11") (pin "1") (pinfunction "1_1") (pintype "passive"))
      (node (ref "C9") (pin "1") (pinfunction "1_1") (pintype "passive"))
      (node (ref "ESIM") (pin "8") (pinfunction "VCC_8") (pintype "power_in"))
      (node (ref "U2") (pin "15") (pinfunction "1Y1_15") (pintype "bidirectional"))
    )
    (net (code "35") (name "NANO_VSIM") (class "Default")
      (node (ref "C2") (pin "1") (pinfunction "1_1") (pintype "passive"))
      (node (ref "C3") (pin "1") (pinfunction "1_1") (pintype "passive"))
      (node (ref "C4") (pin "1") (pinfunction "1_1") (pintype "passive"))
      (node (ref "D1") (pin "6") (pinfunction "Vcc_6") (pintype "power_in"))
      (node (ref "P1") (pin "C1") (pinfunction "VSIM_C1") (pintype "power_in"))
      (node (ref "U2") (pin "1") (pinfunction "1Y0_1") (pintype "bidirectional"))
    )
    (net (code "36") (name "Net-(A1-Pad1)") (class "Default")
      (node (ref "A1") (pin "1") (pinfunction "1_1") (pintype "passive"))
      (node (ref "Z1") (pin "2") (pinfunction "2_2") (pintype "passive"))
      (node (ref "Z2") (pin "2") (pinfunction "2_2") (pintype "passive"))
    )
    (net (code "37") (name "Net-(D7-Anode)") (class "Default")
      (node (ref "D7") (pin "A") (pinfunction "Anode_A") (pintype "passive"))
      (node (ref "R21") (pin "1") (pinfunction "1_1") (pintype "passive"))
    )
    (net (code "38") (name "Net-(D9-Anode)") (class "Default")
      (node (ref "D9") (pin "A") (pinfunction "Anode_A") (pintype "passive"))
      (node (ref "R23") (pin "1") (pinfunction "1_1") (pintype "passive"))
    )
    (net (code "39") (name "Net-(D10-Anode)") (class "Default")
      (node (ref "D10") (pin "A") (pinfunction "Anode_A") (pintype "passive"))
      (node (ref "R24") (pin "1") (pinfunction "1_1") (pintype "passive"))
    )
    (net (code "40") (name "Net-(D11-Anode)") (class "Default")
      (node (ref "D11") (pin "A") (pinfunction "Anode_A") (pintype "passive"))
      (node (ref "R28") (pin "1") (pinfunction "1_1") (pintype "passive"))
    )
    (net (code "41") (name "Net-(D12-Anode)") (class "Default")
      (node (ref "D12") (pin "A") (pinfunction "Anode_A") (pintype "passive"))
      (node (ref "R25") (pin "1") (pinfunction "1_1") (pintype "passive"))
    )
    (net (code "42") (name "Net-(FB1-Pad2)") (class "Default")
      (node (ref "FB1") (pin "2") (pinfunction "2_2") (pintype "passive"))
      (node (ref "U1") (pin "51") (pinfunction "VCC_51") (pintype "power_in"))
      (node (ref "U1") (pin "52") (pinfunction "VCC_52") (pintype "power_in"))
      (node (ref "U1") (pin "53") (pinfunction "VCC_53") (pintype "power_in"))
    )
    (net (code "43") (name "Net-(NC2-Pad2)") (class "Default")
      (node (ref "NC2") (pin "2") (pinfunction "2_2") (pintype "passive"))
      (node (ref "R21") (pin "2") (pinfunction "2_2") (pintype "passive"))
    )
    (net (code "44") (name "Net-(Q4A-D1)") (class "Default")
      (node (ref "Q4") (pin "3") (pinfunction "D2_3") (pintype "passive"))
      (node (ref "Q4") (pin "6") (pinfunction "D1_6") (pintype "passive"))
      (node (ref "U1") (pin "18") (pinfunction "RESET_N_18") (pintype "input"))
    )
    (net (code "45") (name "Net-(Q4A-G1)") (class "Default")
      (node (ref "NC4") (pin "1") (pinfunction "1_1") (pintype "passive"))
      (node (ref "Q4") (pin "2") (pinfunction "G1_2") (pintype "passive"))
      (node (ref "R19") (pin "1") (pinfunction "1_1") (pintype "passive"))
    )
    (net (code "46") (name "Net-(Q5A-D1)") (class "Default")
      (node (ref "Q5") (pin "5") (pinfunction "G2_5") (pintype "passive"))
      (node (ref "Q5") (pin "6") (pinfunction "D1_6") (pintype "passive"))
      (node (ref "R20") (pin "2") (pinfunction "2_2") (pintype "passive"))
    )
    (net (code "47") (name "Net-(Q5B-D2)") (class "Default")
      (node (ref "Q5") (pin "3") (pinfunction "D2_3") (pintype "passive"))
      (node (ref "U1") (pin "33") (pinfunction "EXT_INT_33") (pintype "input"))
    )
    (net (code "48") (name "Net-(Q6A-D1)") (class "Default")
      (node (ref "Q6") (pin "6") (pinfunction "D1_6") (pintype "passive"))
      (node (ref "R23") (pin "2") (pinfunction "2_2") (pintype "passive"))
    )
    (net (code "49") (name "Net-(Q6B-D2)") (class "Default")
      (node (ref "Q6") (pin "3") (pinfunction "D2_3") (pintype "passive"))
      (node (ref "R24") (pin "2") (pinfunction "2_2") (pintype "passive"))
    )
    (net (code "50") (name "Net-(Q7A-D1)") (class "Default")
      (node (ref "Q7") (pin "6") (pinfunction "D1_6") (pintype "passive"))
      (node (ref "R25") (pin "2") (pinfunction "2_2") (pintype "passive"))
    )
    (net (code "51") (name "Net-(Q7B-D2)") (class "Default")
      (node (ref "Q7") (pin "3") (pinfunction "D2_3") (pintype "passive"))
      (node (ref "R28") (pin "2") (pinfunction "2_2") (pintype "passive"))
    )
    (net (code "52") (name "Net-(Q9-D)") (class "Default")
      (node (ref "C36") (pin "1") (pinfunction "1_1") (pintype "passive"))
      (node (ref "J3") (pin "3") (pinfunction "3_3") (pintype "passive"))
      (node (ref "NC2") (pin "1") (pinfunction "1_1") (pintype "passive"))
      (node (ref "NC6") (pin "2") (pinfunction "2_2") (pintype "passive"))
      (node (ref "Q9") (pin "3") (pinfunction "D_3") (pintype "passive"))
    )
    (net (code "53") (name "Net-(Q10A-D1)") (class "Default")
      (node (ref "NO1") (pin "1") (pinfunction "1_1") (pintype "passive"))
      (node (ref "Q10") (pin "6") (pinfunction "D1_6") (pintype "passive"))
      (node (ref "Q9") (pin "1") (pinfunction "G_1") (pintype "passive"))
      (node (ref "R32") (pin "1") (pinfunction "1_1") (pintype "passive"))
    )
    (net (code "54") (name "Net-(Q10B-D2)") (class "Default")
      (node (ref "Q10") (pin "3") (pinfunction "D2_3") (pintype "passive"))
      (node (ref "U1") (pin "15") (pinfunction "PWR_ON_15") (pintype "input"))
    )
    (net (code "55") (name "Net-(Q15A-D1)") (class "Default")
      (node (ref "Q15") (pin "5") (pinfunction "G2_5") (pintype "passive"))
      (node (ref "Q15") (pin "6") (pinfunction "D1_6") (pintype "passive"))
      (node (ref "R49") (pin "2") (pinfunction "2_2") (pintype "passive"))
    )
    (net (code "56") (name "Net-(Q15A-G1)") (class "Default")
      (node (ref "NO3") (pin "1") (pinfunction "1_1") (pintype "passive"))
      (node (ref "Q15") (pin "2") (pinfunction "G1_2") (pintype "passive"))
      (node (ref "R47") (pin "2") (pinfunction "2_2") (pintype "passive"))
    )
    (net (code "57") (name "Net-(Q15B-D2)") (class "Default")
      (node (ref "Q15") (pin "3") (pinfunction "D2_3") (pintype "passive"))
      (node (ref "U1") (pin "17") (pinfunction "VUSB_DET_17") (pintype "input"))
    )
    (net (code "58") (name "Net-(U1-ANT)") (class "Default")
      (node (ref "U1") (pin "56") (pinfunction "ANT_56") (pintype "bidirectional"))
      (node (ref "Z4") (pin "2") (pinfunction "2_2") (pintype "passive"))
      (node (ref "Z6") (pin "1") (pinfunction "1_1") (pintype "passive"))
    )
    (net (code "59") (name "Net-(U1-CTS)") (class "Default")
      (node (ref "U1") (pin "11") (pinfunction "CTS_11") (pintype "output"))
      (node (ref "U4") (pin "12") (pinfunction "B3_12") (pintype "bidirectional"))
    )
    (net (code "60") (name "Net-(U1-DCD)") (class "Default")
      (node (ref "U1") (pin "8") (pinfunction "DCD_8") (pintype "output"))
      (node (ref "U5") (pin "5") (pinfunction "A3_5") (pintype "bidirectional"))
    )
    (net (code "61") (name "Net-(U1-DSR)") (class "Default")
      (node (ref "U1") (pin "6") (pinfunction "DSR_6") (pintype "output"))
      (node (ref "U5") (pin "3") (pinfunction "A1_3") (pintype "bidirectional"))
    )
    (net (code "62") (name "Net-(U1-DTR)") (class "Default")
      (node (ref "U1") (pin "9") (pinfunction "DTR_9") (pintype "input"))
      (node (ref "U5") (pin "6") (pinfunction "A4_6") (pintype "bidirectional"))
    )
    (net (code "63") (name "Net-(U1-RI)") (class "Default")
      (node (ref "U1") (pin "7") (pinfunction "RI_7") (pintype "output"))
      (node (ref "U5") (pin "4") (pinfunction "A2_4") (pintype "bidirectional"))
    )
    (net (code "64") (name "Net-(U1-RTS)") (class "Default")
      (node (ref "U1") (pin "10") (pinfunction "RTS_10") (pintype "input"))
      (node (ref "U4") (pin "11") (pinfunction "B4_11") (pintype "bidirectional"))
    )
    (net (code "65") (name "Net-(U1-RXD)") (class "Default")
      (node (ref "U1") (pin "13") (pinfunction "RXD_13") (pintype "output"))
      (node (ref "U4") (pin "14") (pinfunction "B1_14") (pintype "bidirectional"))
    )
    (net (code "66") (name "Net-(U1-TXD)") (class "Default")
      (node (ref "U1") (pin "12") (pinfunction "TXD_12") (pintype "input"))
      (node (ref "U4") (pin "13") (pinfunction "B2_13") (pintype "bidirectional"))
    )
    (net (code "67") (name "Net-(U4-A3)") (class "Default")
      (node (ref "TP20") (pin "1") (pintype "passive"))
      (node (ref "U4") (pin "5") (pinfunction "A3_5") (pintype "bidirectional"))
    )
    (net (code "68") (name "Net-(U4-A4)") (class "Default")
      (node (ref "TP21") (pin "1") (pintype "passive"))
      (node (ref "U4") (pin "6") (pinfunction "A4_6") (pintype "bidirectional"))
    )
    (net (code "69") (name "Net-(U5-B1)") (class "Default")
      (node (ref "TP22") (pin "1") (pintype "passive"))
      (node (ref "U5") (pin "14") (pinfunction "B1_14") (pintype "bidirectional"))
    )
    (net (code "70") (name "Net-(U5-B2)") (class "Default")
      (node (ref "TP17") (pin "1") (pintype "passive"))
      (node (ref "U5") (pin "13") (pinfunction "B2_13") (pintype "bidirectional"))
    )
    (net (code "71") (name "Net-(Z1-Pad1)") (class "Default")
      (node (ref "Z1") (pin "1") (pinfunction "1_1") (pintype "passive"))
      (node (ref "Z3") (pin "2") (pinfunction "2_2") (pintype "passive"))
      (node (ref "Z4") (pin "1") (pinfunction "1_1") (pintype "passive"))
      (node (ref "Z5") (pin "1") (pinfunction "1_1") (pintype "passive"))
    )
    (net (code "72") (name "SARA_1V8") (class "Default")
      (node (ref "C14") (pin "2") (pinfunction "2_2") (pintype "passive"))
      (node (ref "C15") (pin "1") (pinfunction "1_1") (pintype "passive"))
      (node (ref "C18") (pin "2") (pinfunction "2_2") (pintype "passive"))
      (node (ref "C19") (pin "2") (pinfunction "2_2") (pintype "passive"))
      (node (ref "C8") (pin "2") (pinfunction "2_2") (pintype "passive"))
      (node (ref "NO3") (pin "2") (pinfunction "2_2") (pintype "passive"))
      (node (ref "Q5") (pin "4") (pinfunction "S2_4") (pintype "passive"))
      (node (ref "R1") (pin "2") (pinfunction "2_2") (pintype "passive"))
      (node (ref "R20") (pin "1") (pinfunction "1_1") (pintype "passive"))
      (node (ref "TP10") (pin "1") (pintype "passive"))
      (node (ref "U1") (pin "4") (pinfunction "V_INT_4") (pintype "output"))
      (node (ref "U4") (pin "16") (pinfunction "VCCB_16") (pintype "power_in"))
      (node (ref "U5") (pin "1") (pinfunction "VCCA_1") (pintype "power_in"))
      (node (ref "U5") (pin "10") (pinfunction "DIR3_10") (pintype "input"))
      (node (ref "U5") (pin "15") (pinfunction "DIR2_15") (pintype "input"))
    )
    (net (code "73") (name "SARA_VCC_IN") (class "Default")
      (node (ref "C13") (pin "1") (pinfunction "1_1") (pintype "passive"))
      (node (ref "C23") (pin "2") (pinfunction "2_2") (pintype "passive"))
      (node (ref "C24") (pin "1") (pinfunction "1_1") (pintype "passive"))
      (node (ref "C25") (pin "2") (pinfunction "2_2") (pintype "passive"))
      (node (ref "C26") (pin "2") (pinfunction "2_2") (pintype "passive"))
      (node (ref "C29") (pin "1") (pinfunction "1_1") (pintype "passive"))
      (node (ref "C30") (pin "1") (pinfunction "1_1") (pintype "passive"))
      (node (ref "C31") (pin "1") (pinfunction "1_1") (pintype "passive"))
      (node (ref "C34") (pin "1") (pinfunction "1_1") (pintype "passive"))
      (node (ref "FB1") (pin "1") (pinfunction "1_1") (pintype "passive"))
      (node (ref "J3") (pin "2") (pinfunction "2_2") (pintype "passive"))
      (node (ref "NC6") (pin "1") (pinfunction "1_1") (pintype "passive"))
      (node (ref "TP11") (pin "1") (pintype "passive"))
      (node (ref "U2") (pin "14") (pinfunction "VCC_14") (pintype "power_in"))
    )
    (net (code "74") (name "VBUS") (class "Default")
      (node (ref "Q15") (pin "4") (pinfunction "S2_4") (pintype "passive"))
      (node (ref "R49") (pin "1") (pinfunction "1_1") (pintype "passive"))
    )
    (net (code "75") (name "VSIM") (class "Default")
      (node (ref "TP1") (pin "1") (pintype "passive"))
      (node (ref "U1") (pin "41") (pinfunction "VSIM_41") (pintype "output"))
      (node (ref "U2") (pin "16") (pinfunction "1Z_16") (pintype "bidirectional"))
    )
    (net (code "76") (name "V_BAT") (class "Default")
      (node (ref "Q9") (pin "2") (pinfunction "S_2") (pintype "passive"))
      (node (ref "R32") (pin "2") (pinfunction "2_2") (pintype "passive"))
    )
    (net (code "77") (name "unconnected-(D1-NC-Pad5)") (class "Default")
      (node (ref "D1") (pin "5") (pinfunction "NC_5") (pintype "passive+no_connect"))
    )
    (net (code "78") (name "unconnected-(ESIM-NC-Pad4)") (class "Default")
      (node (ref "ESIM") (pin "4") (pinfunction "NC_4") (pintype "passive+no_connect"))
    )
    (net (code "79") (name "unconnected-(ESIM-NC-Pad5)") (class "Default")
      (node (ref "ESIM") (pin "5") (pinfunction "NC_5") (pintype "passive+no_connect"))
    )
    (net (code "80") (name "unconnected-(ESIM-VPP-Pad2)") (class "Default")
      (node (ref "ESIM") (pin "2") (pinfunction "VPP_2") (pintype "bidirectional+no_connect"))
    )
    (net (code "81") (name "unconnected-(P1-VPP{slash}NC-PadC6)") (class "Default")
      (node (ref "P1") (pin "C6") (pinfunction "VPP/NC_C6") (pintype "bidirectional+no_connect"))
    )
    (net (code "82") (name "unconnected-(U1-ANT_DET-Pad62)") (class "Default")
      (node (ref "U1") (pin "62") (pinfunction "ANT_DET_62") (pintype "input+no_connect"))
    )
    (net (code "83") (name "unconnected-(U1-ANT_GNSS-Pad31)") (class "Default")
      (node (ref "U1") (pin "31") (pinfunction "ANT_GNSS_31") (pintype "input+no_connect"))
    )
    (net (code "84") (name "unconnected-(U1-GND-Pad21)") (class "Default")
      (node (ref "U1") (pin "21") (pinfunction "GND_21") (pintype "power_in+no_connect"))
    )
    (net (code "85") (name "unconnected-(U1-GPIO1-Pad16)") (class "Default")
      (node (ref "U1") (pin "16") (pinfunction "GPIO1_16") (pintype "bidirectional+no_connect"))
    )
    (net (code "86") (name "unconnected-(U1-GPIO3-Pad24)") (class "Default")
      (node (ref "U1") (pin "24") (pinfunction "GPIO3_24") (pintype "bidirectional+no_connect"))
    )
    (net (code "87") (name "unconnected-(U1-GPIO6-Pad19)") (class "Default")
      (node (ref "U1") (pin "19") (pinfunction "GPIO6_19") (pintype "bidirectional+no_connect"))
    )
    (net (code "88") (name "unconnected-(U1-I2S_CLK-Pad36)") (class "Default")
      (node (ref "U1") (pin "36") (pinfunction "I2S_CLK_36") (pintype "output+no_connect"))
    )
    (net (code "89") (name "unconnected-(U1-I2S_RXD-Pad37)") (class "Default")
      (node (ref "U1") (pin "37") (pinfunction "I2S_RXD_37") (pintype "input+no_connect"))
    )
    (net (code "90") (name "unconnected-(U1-I2S_TXD-Pad35)") (class "Default")
      (node (ref "U1") (pin "35") (pinfunction "I2S_TXD_35") (pintype "output+no_connect"))
    )
    (net (code "91") (name "unconnected-(U1-I2S_WA-Pad34)") (class "Default")
      (node (ref "U1") (pin "34") (pinfunction "I2S_WA_34") (pintype "output+no_connect"))
    )
    (net (code "92") (name "unconnected-(U1-RSVD-Pad2)") (class "Default")
      (node (ref "U1") (pin "2") (pinfunction "RSVD_2") (pintype "passive+no_connect"))
    )
    (net (code "93") (name "unconnected-(U1-SDIO_CLK-Pad45)") (class "Default")
      (node (ref "U1") (pin "45") (pinfunction "SDIO_CLK_45") (pintype "output+no_connect"))
    )
    (net (code "94") (name "unconnected-(U1-SDIO_D0{slash}SPI_MOSI-Pad47)") (class "Default")
      (node (ref "U1") (pin "47") (pinfunction "SDIO_D0/SPI_MOSI_47") (pintype "bidirectional+no_connect"))
    )
    (net (code "95") (name "unconnected-(U1-SDIO_D1{slash}SPI_MISO-Pad49)") (class "Default")
      (node (ref "U1") (pin "49") (pinfunction "SDIO_D1/SPI_MISO_49") (pintype "bidirectional+no_connect"))
    )
    (net (code "96") (name "unconnected-(U1-SDIO_D2{slash}SPI_CLK-Pad44)") (class "Default")
      (node (ref "U1") (pin "44") (pinfunction "SDIO_D2/SPI_CLK_44") (pintype "bidirectional+no_connect"))
    )
    (net (code "97") (name "unconnected-(U1-SDIO_D3{slash}SPI_CS-Pad48)") (class "Default")
      (node (ref "U1") (pin "48") (pinfunction "SDIO_D3/SPI_CS_48") (pintype "bidirectional+no_connect"))
    )
    (net (code "98") (name "unconnected-(U2-NC-Pad10)") (class "Default")
      (node (ref "U2") (pin "10") (pinfunction "NC_10") (pintype "passive+no_connect"))
    )
  )
)
